# 06_CapTouch.net
KiCad netlist of a schematic drawn in Altium Designer
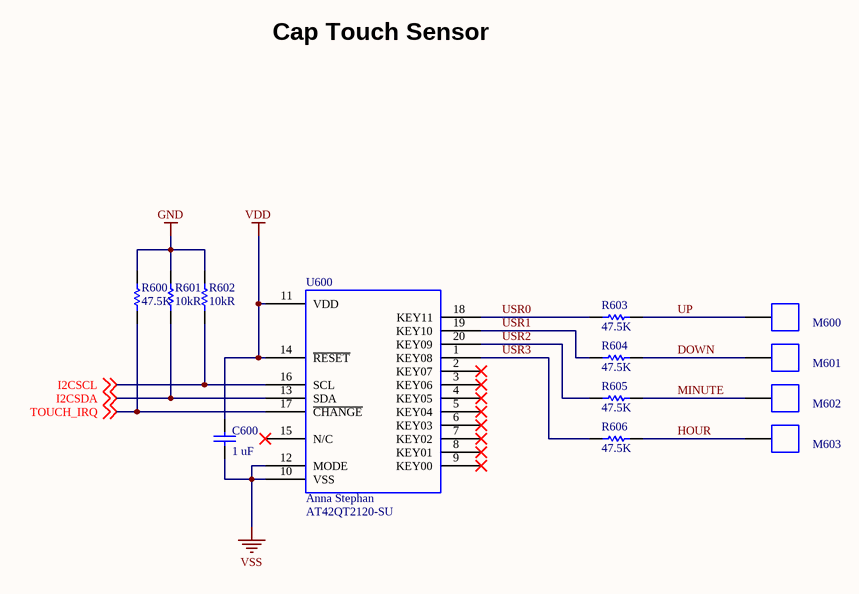
[diagram p0: 06_CapTouch.SchDoc]

(export (version "E")
  (design (tool "Eeschema 10.0.6"))
  (components
    (comp (ref "C600")
      (value "CAP_0805_U_001.00")
      (footprint "CAP_0805")
      (description "CAP CER 1UF 16V 10% X7R 0805")
      (fields
        (field (name "TOLERANCE") "10 %")
        (field (name "MANUFACTURER") "Kemet")
        (field (name "CAPACITANCE") "1 uF")
      )
      (libsource (lib "ece315") (part "CAP_0805_U_001.00"))
    )
    (comp (ref "M600")
      (value "Mech_TouchPad")
      (footprint "TouchPad")
      (description "Capacative Touch Sensor Pad")
      (libsource (lib "ece315-2017-fall") (part "Mech_TouchPad"))
    )
    (comp (ref "M601")
      (value "Mech_TouchPad")
      (footprint "TouchPad")
      (description "Capacative Touch Sensor Pad")
      (libsource (lib "ece315-2017-fall") (part "Mech_TouchPad"))
    )
    (comp (ref "M602")
      (value "Mech_TouchPad")
      (footprint "TouchPad")
      (description "Capacative Touch Sensor Pad")
      (libsource (lib "ece315-2017-fall") (part "Mech_TouchPad"))
    )
    (comp (ref "M603")
      (value "Mech_TouchPad")
      (footprint "TouchPad")
      (description "Capacative Touch Sensor Pad")
      (libsource (lib "ece315-2017-fall") (part "Mech_TouchPad"))
    )
    (comp (ref "R600")
      (value "47.5K")
      (footprint "RES_0805")
      (description "Res Thick Film 2.0 x 1.2 mm 47.5K Ohm 1% 0.125W(1/8W) 100ppm/ C Molded SMD Paper T/R")
      (fields (field (name "TOLERANCE") "1%") (field (name "RESISTANCE") "47.5K"))
      (libsource (lib "ece315") (part "RES_0805_K_047.50"))
    )
    (comp (ref "R601")
      (value "RES_0805_K_010.00")
      (footprint "RES_0805")
      (description "RES SMD 10K OHM 1% 1/8W 0805")
      (fields (field (name "TOLERANCE") "1%") (field (name "RESISTANCE") "10kR"))
      (libsource (lib "ece315") (part "RES_0805_K_010.00"))
    )
    (comp (ref "R602")
      (value "RES_0805_K_010.00")
      (footprint "RES_0805")
      (description "RES SMD 10K OHM 1% 1/8W 0805")
      (fields (field (name "TOLERANCE") "1%") (field (name "RESISTANCE") "10kR"))
      (libsource (lib "ece315") (part "RES_0805_K_010.00"))
    )
    (comp (ref "R603")
      (value "47.5K")
      (footprint "RES_0805")
      (description "Res Thick Film 2.0 x 1.2 mm 47.5K Ohm 1% 0.125W(1/8W) 100ppm/ C Molded SMD Paper T/R")
      (fields (field (name "TOLERANCE") "1%") (field (name "RESISTANCE") "47.5K"))
      (libsource (lib "ece315") (part "RES_0805_K_047.50"))
    )
    (comp (ref "R604")
      (value "47.5K")
      (footprint "RES_0805")
      (description "Res Thick Film 2.0 x 1.2 mm 47.5K Ohm 1% 0.125W(1/8W) 100ppm/ C Molded SMD Paper T/R")
      (fields (field (name "TOLERANCE") "1%") (field (name "RESISTANCE") "47.5K"))
      (libsource (lib "ece315") (part "RES_0805_K_047.50"))
    )
    (comp (ref "R605")
      (value "47.5K")
      (footprint "RES_0805")
      (description "Res Thick Film 2.0 x 1.2 mm 47.5K Ohm 1% 0.125W(1/8W) 100ppm/ C Molded SMD Paper T/R")
      (fields (field (name "TOLERANCE") "1%") (field (name "RESISTANCE") "47.5K"))
      (libsource (lib "ece315") (part "RES_0805_K_047.50"))
    )
    (comp (ref "R606")
      (value "47.5K")
      (footprint "RES_0805")
      (description "Res Thick Film 2.0 x 1.2 mm 47.5K Ohm 1% 0.125W(1/8W) 100ppm/ C Molded SMD Paper T/R")
      (fields (field (name "TOLERANCE") "1%") (field (name "RESISTANCE") "47.5K"))
      (libsource (lib "ece315") (part "RES_0805_K_047.50"))
    )
    (comp (ref "U600")
      (value "IC_AT42QT2120")
      (footprint "AT42QT2120-SOIC")
      (description "IC TOUCH SENSOR 12CH 20SOIC")
      (fields
        (field (name "DRAWN_BY") "Anna Stephan")
        (field (name "MANUFACTURER PART NUMBER 1") "AT42QT2120-SU")
      )
      (libsource (lib "ece315") (part "AT42QT2120"))
    )
  )
  (nets
    (net (code "1") (name "/DOWN") (class "Default")
      (node (ref "M601") (pin "1") (pinfunction "1_1") (pintype "passive"))
      (node (ref "R604") (pin "1") (pinfunction "1_1") (pintype "passive"))
    )
    (net (code "2") (name "/HOUR") (class "Default")
      (node (ref "M603") (pin "1") (pinfunction "1_1") (pintype "passive"))
      (node (ref "R606") (pin "1") (pinfunction "1_1") (pintype "passive"))
    )
    (net (code "3") (name "/MINUTE") (class "Default")
      (node (ref "M602") (pin "1") (pinfunction "1_1") (pintype "passive"))
      (node (ref "R605") (pin "1") (pinfunction "1_1") (pintype "passive"))
    )
    (net (code "4") (name "/UP") (class "Default")
      (node (ref "M600") (pin "1") (pinfunction "1_1") (pintype "passive"))
      (node (ref "R603") (pin "1") (pinfunction "1_1") (pintype "passive"))
    )
    (net (code "5") (name "/USR0") (class "Default")
      (node (ref "R603") (pin "2") (pinfunction "2_2") (pintype "passive"))
      (node (ref "U600") (pin "18") (pinfunction "KEY11_18") (pintype "passive"))
    )
    (net (code "6") (name "/USR1") (class "Default")
      (node (ref "R604") (pin "2") (pinfunction "2_2") (pintype "passive"))
      (node (ref "U600") (pin "19") (pinfunction "KEY10_19") (pintype "passive"))
    )
    (net (code "7") (name "/USR2") (class "Default")
      (node (ref "R605") (pin "2") (pinfunction "2_2") (pintype "passive"))
      (node (ref "U600") (pin "20") (pinfunction "KEY09_20") (pintype "passive"))
    )
    (net (code "8") (name "/USR3") (class "Default")
      (node (ref "R606") (pin "2") (pinfunction "2_2") (pintype "passive"))
      (node (ref "U600") (pin "1") (pinfunction "KEY08_1") (pintype "passive"))
    )
    (net (code "9") (name "GND") (class "Default")
      (node (ref "R600") (pin "2") (pinfunction "2_2") (pintype "passive"))
      (node (ref "R601") (pin "2") (pinfunction "2_2") (pintype "passive"))
      (node (ref "R602") (pin "2") (pinfunction "2_2") (pintype "passive"))
    )
    (net (code "10") (name "I2CSCL") (class "Default")
      (node (ref "R602") (pin "1") (pinfunction "1_1") (pintype "passive"))
      (node (ref "U600") (pin "16") (pinfunction "SCL_16") (pintype "passive"))
    )
    (net (code "11") (name "I2CSDA") (class "Default")
      (node (ref "R601") (pin "1") (pinfunction "1_1") (pintype "passive"))
      (node (ref "U600") (pin "13") (pinfunction "SDA_13") (pintype "passive"))
    )
    (net (code "12") (name "TOUCH_IRQ") (class "Default")
      (node (ref "R600") (pin "1") (pinfunction "1_1") (pintype "passive"))
      (node (ref "U600") (pin "17") (pinfunction "~{CHANGE}_17") (pintype "passive"))
    )
    (net (code "13") (name "VDD") (class "Default")
      (node (ref "C600") (pin "1") (pinfunction "1_1") (pintype "passive"))
      (node (ref "U600") (pin "11") (pinfunction "VDD_11") (pintype "passive"))
      (node (ref "U600") (pin "14") (pinfunction "~{RESET}_14") (pintype "passive"))
    )
    (net (code "14") (name "VSS") (class "Default")
      (node (ref "C600") (pin "2") (pinfunction "2_2") (pintype "passive"))
      (node (ref "U600") (pin "10") (pinfunction "VSS_10") (pintype "passive"))
      (node (ref "U600") (pin "12") (pinfunction "MODE_12") (pintype "passive"))
    )
    (net (code "15") (name "unconnected-(U600-KEY00-Pad9)") (class "Default")
      (node (ref "U600") (pin "9") (pinfunction "KEY00_9") (pintype "passive+no_connect"))
    )
    (net (code "16") (name "unconnected-(U600-KEY01-Pad8)") (class "Default")
      (node (ref "U600") (pin "8") (pinfunction "KEY01_8") (pintype "passive+no_connect"))
    )
    (net (code "17") (name "unconnected-(U600-KEY02-Pad7)") (class "Default")
      (node (ref "U600") (pin "7") (pinfunction "KEY02_7") (pintype "passive+no_connect"))
    )
    (net (code "18") (name "unconnected-(U600-KEY03-Pad6)") (class "Default")
      (node (ref "U600") (pin "6") (pinfunction "KEY03_6") (pintype "passive+no_connect"))
    )
    (net (code "19") (name "unconnected-(U600-KEY04-Pad5)") (class "Default")
      (node (ref "U600") (pin "5") (pinfunction "KEY04_5") (pintype "passive+no_connect"))
    )
    (net (code "20") (name "unconnected-(U600-KEY05-Pad4)") (class "Default")
      (node (ref "U600") (pin "4") (pinfunction "KEY05_4") (pintype "passive+no_connect"))
    )
    (net (code "21") (name "unconnected-(U600-KEY06-Pad3)") (class "Default")
      (node (ref "U600") (pin "3") (pinfunction "KEY06_3") (pintype "passive+no_connect"))
    )
    (net (code "22") (name "unconnected-(U600-KEY07-Pad2)") (class "Default")
      (node (ref "U600") (pin "2") (pinfunction "KEY07_2") (pintype "passive+no_connect"))
    )
    (net (code "23") (name "unconnected-(U600-N{slash}C-Pad15)") (class "Default")
      (node (ref "U600") (pin "15") (pinfunction "N/C_15") (pintype "passive+no_connect"))
    )
  )
)
